# 05_OSC_PLL.net
KiCad netlist of a schematic drawn in Altium Designer
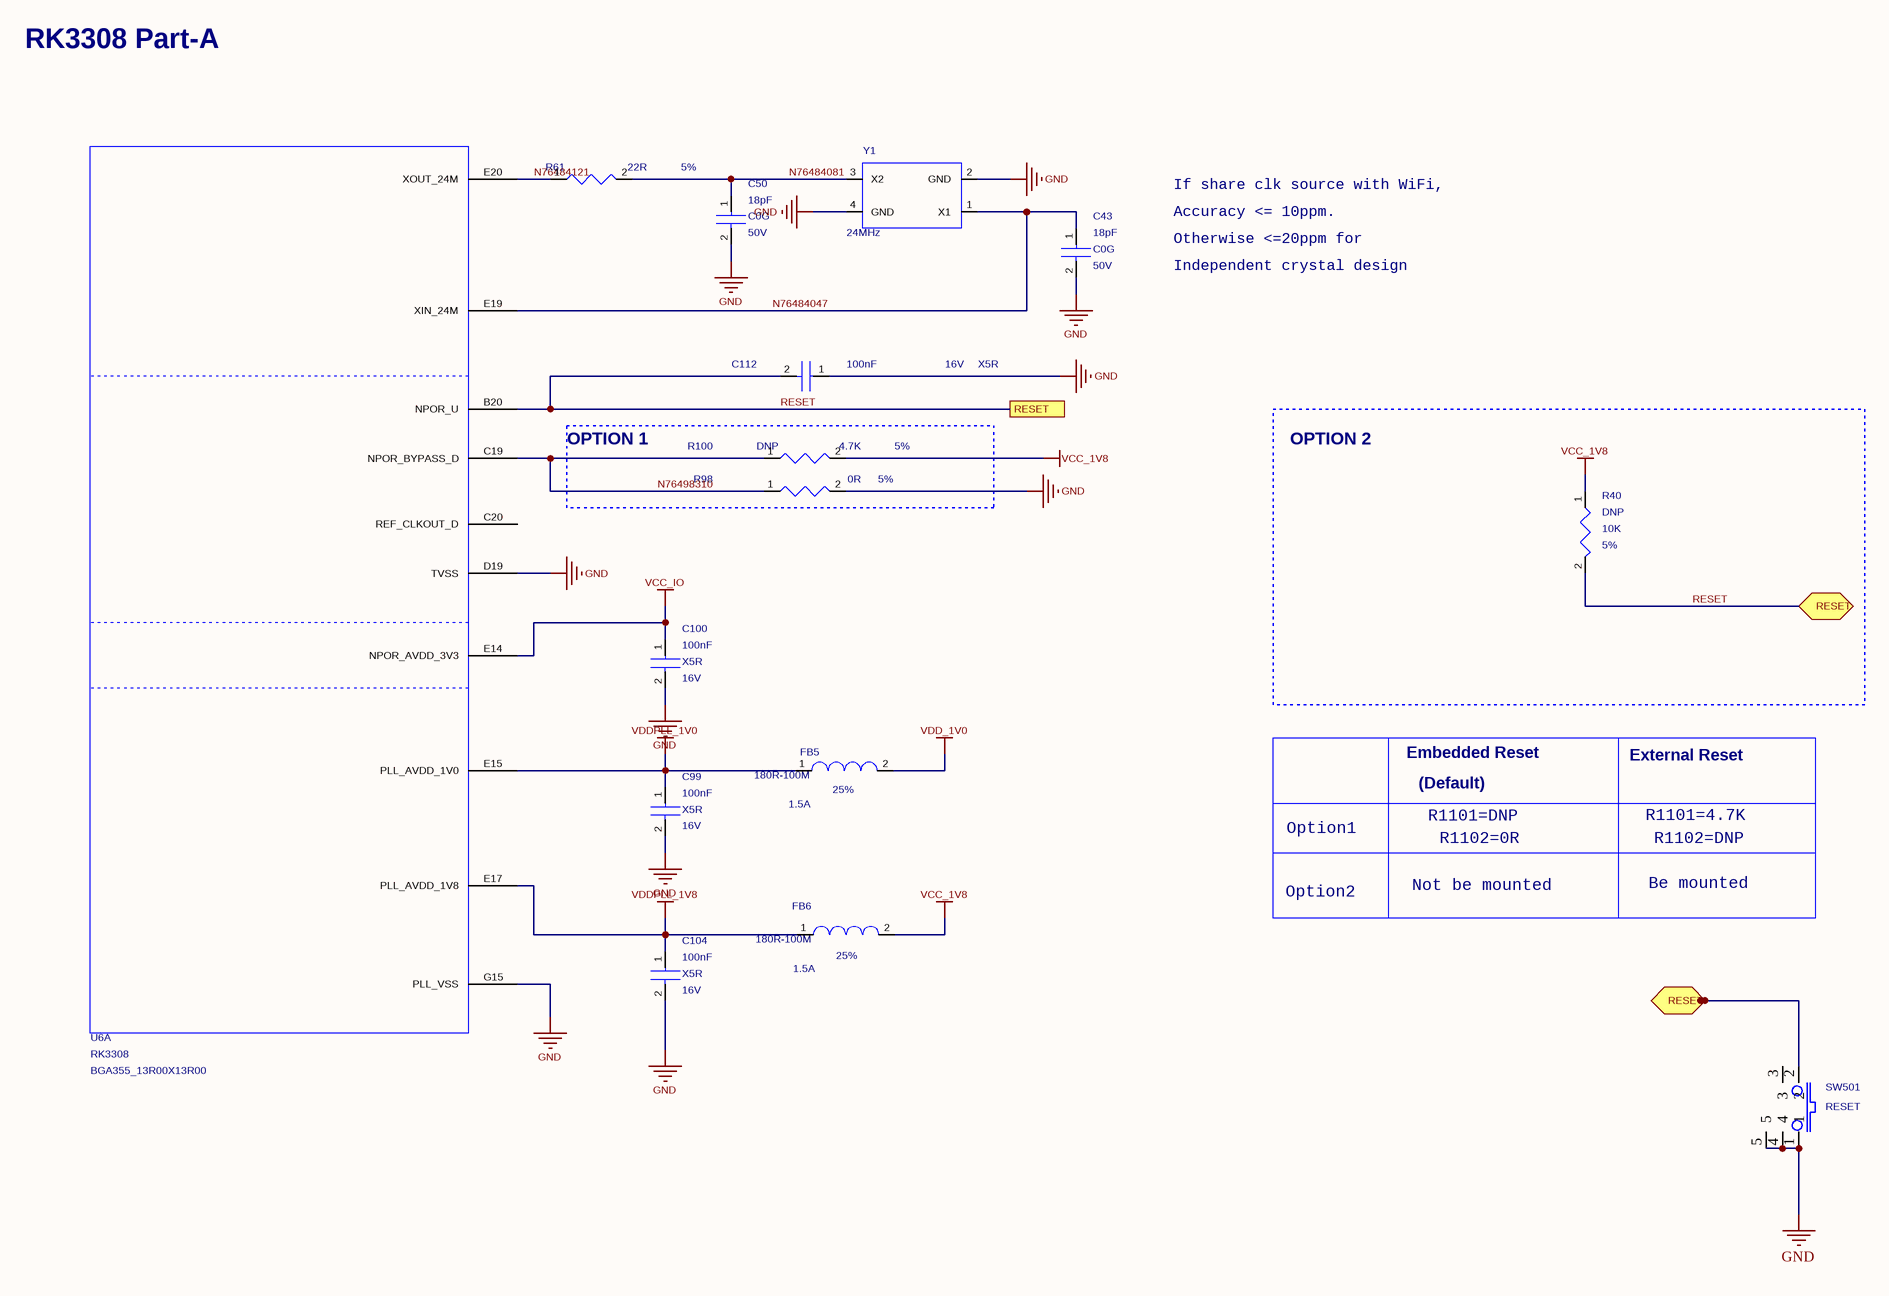
[diagram p0: 05_OSC_PLL.SchDoc]

(export (version "E")
  (design (tool "Eeschema 10.0.6"))
  (components
    (comp (ref "C43")
      (value "18pF")
      (footprint "C0402")
      (description "cap,18.00pF,+/-5%,50V,C0G,C0402")
      (fields
        (field (name "DIELECTRIC") "C0G")
        (field (name "TOLERANCE") "5%")
        (field (name "MANUFACTURER") "TDK")
        (field (name "VOLTAGE") "50V")
        (field (name "CREATED_BY") "JJJ")
      )
      (libsource (lib "*") (part "CAP_NP_2"))
    )
    (comp (ref "C50")
      (value "18pF")
      (footprint "C0402")
      (description "cap,18.00pF,+/-5%,50V,C0G,C0402")
      (fields
        (field (name "DIELECTRIC") "C0G")
        (field (name "TOLERANCE") "5%")
        (field (name "MANUFACTURER") "TDK")
        (field (name "VOLTAGE") "50V")
        (field (name "CREATED_BY") "JJJ")
      )
      (libsource (lib "*") (part "CAP_NP_2"))
    )
    (comp (ref "C99")
      (value "100nF")
      (footprint "C0402")
      (description "cap,100.00nF,+/-10%,16V,X5R,C0402")
      (fields
        (field (name "MANUFACTURER") "TDK")
        (field (name "TOLERANCE") "10%")
        (field (name "VOLTAGE") "16V")
        (field (name "DIELECTRIC") "X5R")
        (field (name "CREATED_BY") "JJJ")
      )
      (libsource (lib "*") (part "CAP_NP_2"))
    )
    (comp (ref "C100")
      (value "100nF")
      (footprint "C0402")
      (description "cap,100.00nF,+/-10%,16V,X5R,C0402")
      (fields
        (field (name "MANUFACTURER") "TDK")
        (field (name "TOLERANCE") "10%")
        (field (name "VOLTAGE") "16V")
        (field (name "DIELECTRIC") "X5R")
        (field (name "CREATED_BY") "JJJ")
      )
      (libsource (lib "*") (part "CAP_NP_2"))
    )
    (comp (ref "C104")
      (value "100nF")
      (footprint "C0402")
      (description "cap,100.00nF,+/-10%,16V,X5R,C0402")
      (fields
        (field (name "MANUFACTURER") "TDK")
        (field (name "TOLERANCE") "10%")
        (field (name "VOLTAGE") "16V")
        (field (name "DIELECTRIC") "X5R")
        (field (name "CREATED_BY") "JJJ")
      )
      (libsource (lib "*") (part "CAP_NP_2"))
    )
    (comp (ref "C112")
      (value "100nF")
      (footprint "C0402")
      (description "cap,100.00nF,+/-10%,16V,X5R,C0402")
      (fields
        (field (name "DIELECTRIC") "X5R")
        (field (name "VOLTAGE") "16V")
        (field (name "TOLERANCE") "10%")
        (field (name "MANUFACTURER") "TDK")
        (field (name "CREATED_BY") "JJJ")
      )
      (libsource (lib "*") (part "CAP_NP_2"))
    )
    (comp (ref "FB5")
      (value "180R-100M")
      (footprint "L0603")
      (description "Ferrite Bead,180R-100M,0.25,L0603")
      (fields
        (field (name "TOLERANCE") "25%")
        (field (name "IRMS") "1.5A")
        (field (name "MANUFACTURER") "Murata")
        (field (name "Comment") "BEAD")
        (field (name "CREATED_BY") "YTL")
      )
      (libsource (lib "*") (part "BEAD"))
    )
    (comp (ref "FB6")
      (value "180R-100M")
      (footprint "L0603")
      (description "Ferrite Bead,180R-100M,0.25,L0603")
      (fields
        (field (name "TOLERANCE") "25%")
        (field (name "IRMS") "1.5A")
        (field (name "MANUFACTURER") "Murata")
        (field (name "Comment") "BEAD")
        (field (name "CREATED_BY") "YTL")
      )
      (libsource (lib "*") (part "BEAD"))
    )
    (comp (ref "R40")
      (value "10K")
      (footprint "R0402")
      (description "?用厚膜电阻,10K,+/-5%,R0402,1/16W.")
      (fields
        (field (name "OPTION") "DNP")
        (field (name "MANUFACTURER") "YAGEO")
        (field (name "TOLERANCE") "5%")
        (field (name "Comment") "RESISTOR")
        (field (name "CREATED_BY") "YTL")
      )
      (libsource (lib "*") (part "RESISTOR"))
    )
    (comp (ref "R61")
      (value "22R")
      (footprint "R0402")
      (description "?用厚膜电阻,22R,+/-5%,R0402,1/16W.")
      (fields
        (field (name "MANUFACTURER") "YAGEO")
        (field (name "TOLERANCE") "5%")
        (field (name "Comment") "RESISTOR")
        (field (name "CREATED_BY") "YTL")
      )
      (libsource (lib "*") (part "RESISTOR"))
    )
    (comp (ref "R98")
      (value "0R")
      (footprint "R0402")
      (description "?用厚膜电阻,0R,+/-5%,R0402,1/16W.")
      (fields
        (field (name "MANUFACTURER") "YAGEO")
        (field (name "TOLERANCE") "5%")
        (field (name "Comment") "RESISTOR")
        (field (name "CREATED_BY") "YTL")
      )
      (libsource (lib "*") (part "RESISTOR"))
    )
    (comp (ref "R100")
      (value "4.7K")
      (footprint "R0402")
      (description "?用厚膜电阻,4K7,+/-5%,R0402,1/16W.")
      (fields
        (field (name "MANUFACTURER") "YAGEO")
        (field (name "TOLERANCE") "5%")
        (field (name "OPTION") "DNP")
        (field (name "Comment") "RESISTOR")
        (field (name "CREATED_BY") "YTL")
      )
      (libsource (lib "*") (part "RESISTOR"))
    )
    (comp (ref "SW501")
      (value "RESET")
      (footprint "SW-TS")
      (description "TS-1086EV-AR03526")
      (fields
        (field (name "MANUFACTURER") "褀华电子")
        (field (name "MANUFACTURER PART NUMBER") "TS-1125S")
        (field (name "CREATED BY") "YWQ")
      )
      (libsource (lib "*") (part "KEY_5PIN"))
    )
    (comp (ref "U6")
      (value "RK3308")
      (footprint "BGA355_13R00X13R00")
      (fields (field (name "PCB DECAL") "BGA355_13R00X13R00") (field (name "MANUFACTURER") "ROCKCHIP"))
      (libsource (lib "*") (part "RK3308"))
    )
    (comp (ref "Y1")
      (value "24MHz")
      (footprint "CRY4_3R20X2R50X0R80")
      (description "无源晶振，24M，3225,±10ppm，12pF，Hosonic")
      (fields
        (field (name "MANUFACTURER") "Hosonic(鸿星电子)")
        (field (name "Comment") "CRYSTAL_4P")
        (field (name "CREATED_BY") "JJJ")
      )
      (libsource (lib "*") (part "CRYSTAL_4P"))
    )
  )
  (nets
    (net (code "1") (name "/N76484047") (class "Default")
      (node (ref "C43") (pin "1") (pinfunction "1_1") (pintype "passive"))
      (node (ref "U6") (pin "E19") (pinfunction "XIN_24M_E19") (pintype "passive"))
      (node (ref "Y1") (pin "1") (pinfunction "X1_1") (pintype "passive"))
    )
    (net (code "2") (name "/N76484081") (class "Default")
      (node (ref "C50") (pin "1") (pinfunction "1_1") (pintype "passive"))
      (node (ref "R61") (pin "2") (pinfunction "2_2") (pintype "passive"))
      (node (ref "Y1") (pin "3") (pinfunction "X2_3") (pintype "passive"))
    )
    (net (code "3") (name "/N76484121") (class "Default")
      (node (ref "R61") (pin "1") (pinfunction "1_1") (pintype "passive"))
      (node (ref "U6") (pin "E20") (pinfunction "XOUT_24M_E20") (pintype "passive"))
    )
    (net (code "4") (name "/N76498310") (class "Default")
      (node (ref "R100") (pin "1") (pinfunction "1_1") (pintype "passive"))
      (node (ref "R98") (pin "1") (pinfunction "1_1") (pintype "passive"))
      (node (ref "U6") (pin "C19") (pinfunction "NPOR_BYPASS_D_C19") (pintype "passive"))
    )
    (net (code "5") (name "/RESET") (class "Default")
      (node (ref "C112") (pin "2") (pinfunction "2_2") (pintype "passive"))
      (node (ref "R40") (pin "2") (pinfunction "2_2") (pintype "passive"))
      (node (ref "SW501") (pin "2") (pinfunction "2_2") (pintype "passive"))
      (node (ref "U6") (pin "B20") (pinfunction "NPOR_U_B20") (pintype "passive"))
    )
    (net (code "6") (name "GND") (class "Default")
      (node (ref "C100") (pin "2") (pinfunction "2_2") (pintype "passive"))
      (node (ref "C104") (pin "2") (pinfunction "2_2") (pintype "passive"))
      (node (ref "C112") (pin "1") (pinfunction "1_1") (pintype "passive"))
      (node (ref "C43") (pin "2") (pinfunction "2_2") (pintype "passive"))
      (node (ref "C50") (pin "2") (pinfunction "2_2") (pintype "passive"))
      (node (ref "C99") (pin "2") (pinfunction "2_2") (pintype "passive"))
      (node (ref "R98") (pin "2") (pinfunction "2_2") (pintype "passive"))
      (node (ref "SW501") (pin "1") (pinfunction "1_1") (pintype "passive"))
      (node (ref "SW501") (pin "4") (pinfunction "4_4") (pintype "passive"))
      (node (ref "SW501") (pin "5") (pinfunction "5_5") (pintype "passive"))
      (node (ref "U6") (pin "D19") (pinfunction "TVSS_D19") (pintype "passive"))
      (node (ref "U6") (pin "G15") (pinfunction "PLL_VSS_G15") (pintype "passive"))
      (node (ref "Y1") (pin "2") (pinfunction "GND_2") (pintype "power_in"))
      (node (ref "Y1") (pin "4") (pinfunction "GND_4") (pintype "power_in"))
    )
    (net (code "7") (name "VCC_1V8") (class "Default")
      (node (ref "FB6") (pin "2") (pinfunction "2_2") (pintype "passive"))
      (node (ref "R100") (pin "2") (pinfunction "2_2") (pintype "passive"))
      (node (ref "R40") (pin "1") (pinfunction "1_1") (pintype "passive"))
    )
    (net (code "8") (name "VCC_IO") (class "Default")
      (node (ref "C100") (pin "1") (pinfunction "1_1") (pintype "passive"))
      (node (ref "U6") (pin "E14") (pinfunction "NPOR_AVDD_3V3_E14") (pintype "passive"))
    )
    (net (code "9") (name "VDDPLL_1V0") (class "Default")
      (node (ref "C99") (pin "1") (pinfunction "1_1") (pintype "passive"))
      (node (ref "FB5") (pin "1") (pinfunction "1_1") (pintype "passive"))
      (node (ref "U6") (pin "E15") (pinfunction "PLL_AVDD_1V0_E15") (pintype "passive"))
    )
    (net (code "10") (name "VDDPLL_1V8") (class "Default")
      (node (ref "C104") (pin "1") (pinfunction "1_1") (pintype "passive"))
      (node (ref "FB6") (pin "1") (pinfunction "1_1") (pintype "passive"))
      (node (ref "U6") (pin "E17") (pinfunction "PLL_AVDD_1V8_E17") (pintype "passive"))
    )
    (net (code "11") (name "VDD_1V0") (class "Default")
      (node (ref "FB5") (pin "2") (pinfunction "2_2") (pintype "passive"))
    )
    (net (code "12") (name "unconnected-(SW501-Pad3)") (class "Default")
      (node (ref "SW501") (pin "3") (pinfunction "3_3") (pintype "passive"))
    )
    (net (code "13") (name "unconnected-(U6A-REF_CLKOUT_D-PadC20)") (class "Default")
      (node (ref "U6") (pin "C20") (pinfunction "REF_CLKOUT_D_C20") (pintype "passive"))
    )
  )
)
